# SR-et-Supply.net
KiCad netlist of a schematic drawn in EAGLE
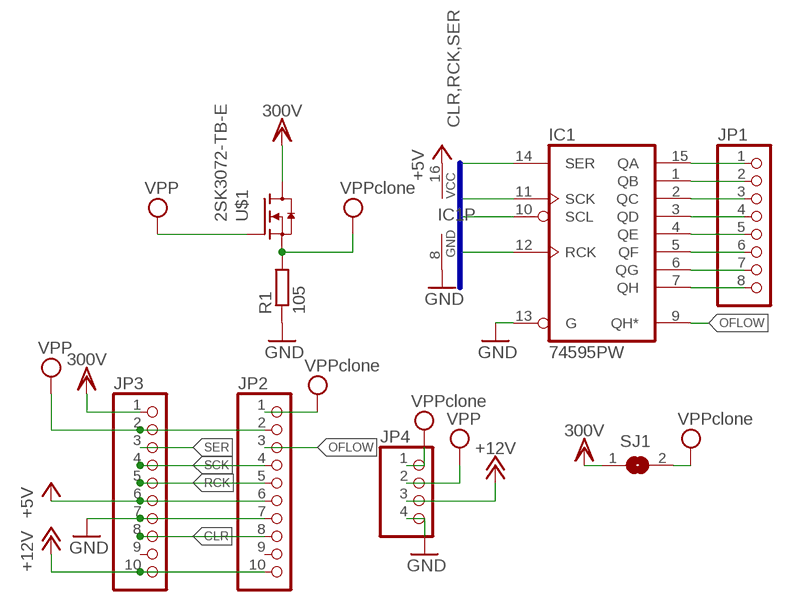
[diagram p0: schematic, sheet 1]

(export (version "E")
  (design (tool "Eeschema 10.0.6"))
  (components
    (comp (ref "IC1")
      (value "74595PW")
      (footprint "eagle-import:TTSOP16")
      (libsource (lib "eagle-import") (part "74595PW"))
    )
    (comp (ref "JP1")
      (value "PINHD-1X8")
      (footprint "eagle-import:1X08")
      (libsource (lib "eagle-import") (part "PINHD-1X8"))
    )
    (comp (ref "JP2")
      (value "PINHD-1X10")
      (footprint "eagle-import:1X10")
      (libsource (lib "eagle-import") (part "PINHD-1X10"))
    )
    (comp (ref "JP3")
      (value "PINHD-1X10")
      (footprint "eagle-import:1X10")
      (libsource (lib "eagle-import") (part "PINHD-1X10"))
    )
    (comp (ref "JP4")
      (value "PINHD-1X4")
      (footprint "eagle-import:1X04")
      (libsource (lib "eagle-import") (part "PINHD-1X4"))
    )
    (comp (ref "R1")
      (value "105")
      (footprint "eagle-import:0204_5")
      (libsource (lib "eagle-import") (part "R-EU_0204/5"))
    )
    (comp (ref "SJ1") (value "SJ") (footprint "eagle-import:SJ") (libsource (lib "eagle-import") (part "SJ")))
    (comp (ref "U$1")
      (value "2SK3072-TB-E")
      (footprint "eagle-import:SOT95P250X120-3")
      (libsource (lib "eagle-import") (part "2SK3072-TB-E"))
    )
  )
  (nets
    (net (code "1") (name "+5V") (class "Default")
      (node (ref "IC1") (pin "16") (pinfunction "VCC_16") (pintype "power_in"))
      (node (ref "JP2") (pin "6") (pinfunction "6_6") (pintype "passive"))
      (node (ref "JP3") (pin "6") (pinfunction "6_6") (pintype "passive"))
    )
    (net (code "2") (name "+12V") (class "Default")
      (node (ref "JP2") (pin "10") (pinfunction "10_10") (pintype "passive"))
      (node (ref "JP3") (pin "10") (pinfunction "10_10") (pintype "passive"))
      (node (ref "JP4") (pin "3") (pinfunction "3_3") (pintype "passive"))
    )
    (net (code "4") (name "300V") (class "Default")
      (node (ref "JP3") (pin "1") (pinfunction "1_1") (pintype "passive"))
      (node (ref "SJ1") (pin "1") (pinfunction "1_1") (pintype "passive"))
      (node (ref "U$1") (pin "3") (pinfunction "D_3") (pintype "passive"))
    )
    (net (code "5") (name "CLR") (class "Default")
      (node (ref "IC1") (pin "10") (pinfunction "SCL_10") (pintype "input"))
      (node (ref "JP2") (pin "8") (pinfunction "8_8") (pintype "passive"))
      (node (ref "JP3") (pin "8") (pinfunction "8_8") (pintype "passive"))
    )
    (net (code "6") (name "GND") (class "Default")
      (node (ref "IC1") (pin "13") (pinfunction "G_13") (pintype "input"))
      (node (ref "IC1") (pin "8") (pinfunction "GND_8") (pintype "power_in"))
      (node (ref "JP2") (pin "7") (pinfunction "7_7") (pintype "passive"))
      (node (ref "JP3") (pin "7") (pinfunction "7_7") (pintype "passive"))
      (node (ref "JP4") (pin "4") (pinfunction "4_4") (pintype "passive"))
      (node (ref "R1") (pin "1") (pinfunction "1_1") (pintype "passive"))
    )
    (net (code "7") (name "Net-(IC1A-QA)") (class "Default")
      (node (ref "IC1") (pin "15") (pinfunction "QA_15") (pintype "tri_state"))
      (node (ref "JP1") (pin "1") (pinfunction "1_1") (pintype "passive"))
    )
    (net (code "8") (name "Net-(IC1A-QB)") (class "Default")
      (node (ref "IC1") (pin "1") (pinfunction "QB_1") (pintype "tri_state"))
      (node (ref "JP1") (pin "2") (pinfunction "2_2") (pintype "passive"))
    )
    (net (code "9") (name "Net-(IC1A-QC)") (class "Default")
      (node (ref "IC1") (pin "2") (pinfunction "QC_2") (pintype "tri_state"))
      (node (ref "JP1") (pin "3") (pinfunction "3_3") (pintype "passive"))
    )
    (net (code "10") (name "Net-(IC1A-QD)") (class "Default")
      (node (ref "IC1") (pin "3") (pinfunction "QD_3") (pintype "tri_state"))
      (node (ref "JP1") (pin "4") (pinfunction "4_4") (pintype "passive"))
    )
    (net (code "11") (name "Net-(IC1A-QE)") (class "Default")
      (node (ref "IC1") (pin "4") (pinfunction "QE_4") (pintype "tri_state"))
      (node (ref "JP1") (pin "5") (pinfunction "5_5") (pintype "passive"))
    )
    (net (code "12") (name "Net-(IC1A-QF)") (class "Default")
      (node (ref "IC1") (pin "5") (pinfunction "QF_5") (pintype "tri_state"))
      (node (ref "JP1") (pin "6") (pinfunction "6_6") (pintype "passive"))
    )
    (net (code "13") (name "Net-(IC1A-QG)") (class "Default")
      (node (ref "IC1") (pin "6") (pinfunction "QG_6") (pintype "tri_state"))
      (node (ref "JP1") (pin "7") (pinfunction "7_7") (pintype "passive"))
    )
    (net (code "14") (name "Net-(IC1A-QH)") (class "Default")
      (node (ref "IC1") (pin "7") (pinfunction "QH_7") (pintype "tri_state"))
      (node (ref "JP1") (pin "8") (pinfunction "8_8") (pintype "passive"))
    )
    (net (code "15") (name "OFLOW") (class "Default")
      (node (ref "IC1") (pin "9") (pinfunction "QH*_9") (pintype "tri_state"))
      (node (ref "JP2") (pin "3") (pinfunction "3_3") (pintype "passive"))
    )
    (net (code "16") (name "RCK") (class "Default")
      (node (ref "IC1") (pin "12") (pinfunction "RCK_12") (pintype "input"))
      (node (ref "JP2") (pin "5") (pinfunction "5_5") (pintype "passive"))
      (node (ref "JP3") (pin "5") (pinfunction "5_5") (pintype "passive"))
    )
    (net (code "17") (name "SCK") (class "Default")
      (node (ref "IC1") (pin "11") (pinfunction "SCK_11") (pintype "input"))
      (node (ref "JP2") (pin "4") (pinfunction "4_4") (pintype "passive"))
      (node (ref "JP3") (pin "4") (pinfunction "4_4") (pintype "passive"))
    )
    (net (code "18") (name "SER") (class "Default")
      (node (ref "IC1") (pin "14") (pinfunction "SER_14") (pintype "input"))
      (node (ref "JP3") (pin "3") (pinfunction "3_3") (pintype "passive"))
    )
    (net (code "19") (name "VPP") (class "Default")
      (node (ref "JP2") (pin "2") (pinfunction "2_2") (pintype "passive"))
      (node (ref "JP3") (pin "2") (pinfunction "2_2") (pintype "passive"))
      (node (ref "JP4") (pin "2") (pinfunction "2_2") (pintype "passive"))
      (node (ref "U$1") (pin "1") (pinfunction "G_1") (pintype "passive"))
    )
    (net (code "20") (name "VPPclone") (class "Default")
      (node (ref "JP2") (pin "1") (pinfunction "1_1") (pintype "passive"))
      (node (ref "JP4") (pin "1") (pinfunction "1_1") (pintype "passive"))
      (node (ref "R1") (pin "2") (pinfunction "2_2") (pintype "passive"))
      (node (ref "SJ1") (pin "2") (pinfunction "2_2") (pintype "passive"))
      (node (ref "U$1") (pin "2") (pinfunction "S_2") (pintype "passive"))
    )
    (net (code "21") (name "unconnected-(JP2-Pad9)") (class "Default")
      (node (ref "JP2") (pin "9") (pinfunction "9_9") (pintype "passive"))
    )
    (net (code "22") (name "unconnected-(JP3-Pad9)") (class "Default")
      (node (ref "JP3") (pin "9") (pinfunction "9_9") (pintype "passive"))
    )
  )
)
